# MotorController_ToniDove_Full06.net
KiCad netlist of a schematic drawn in EAGLE
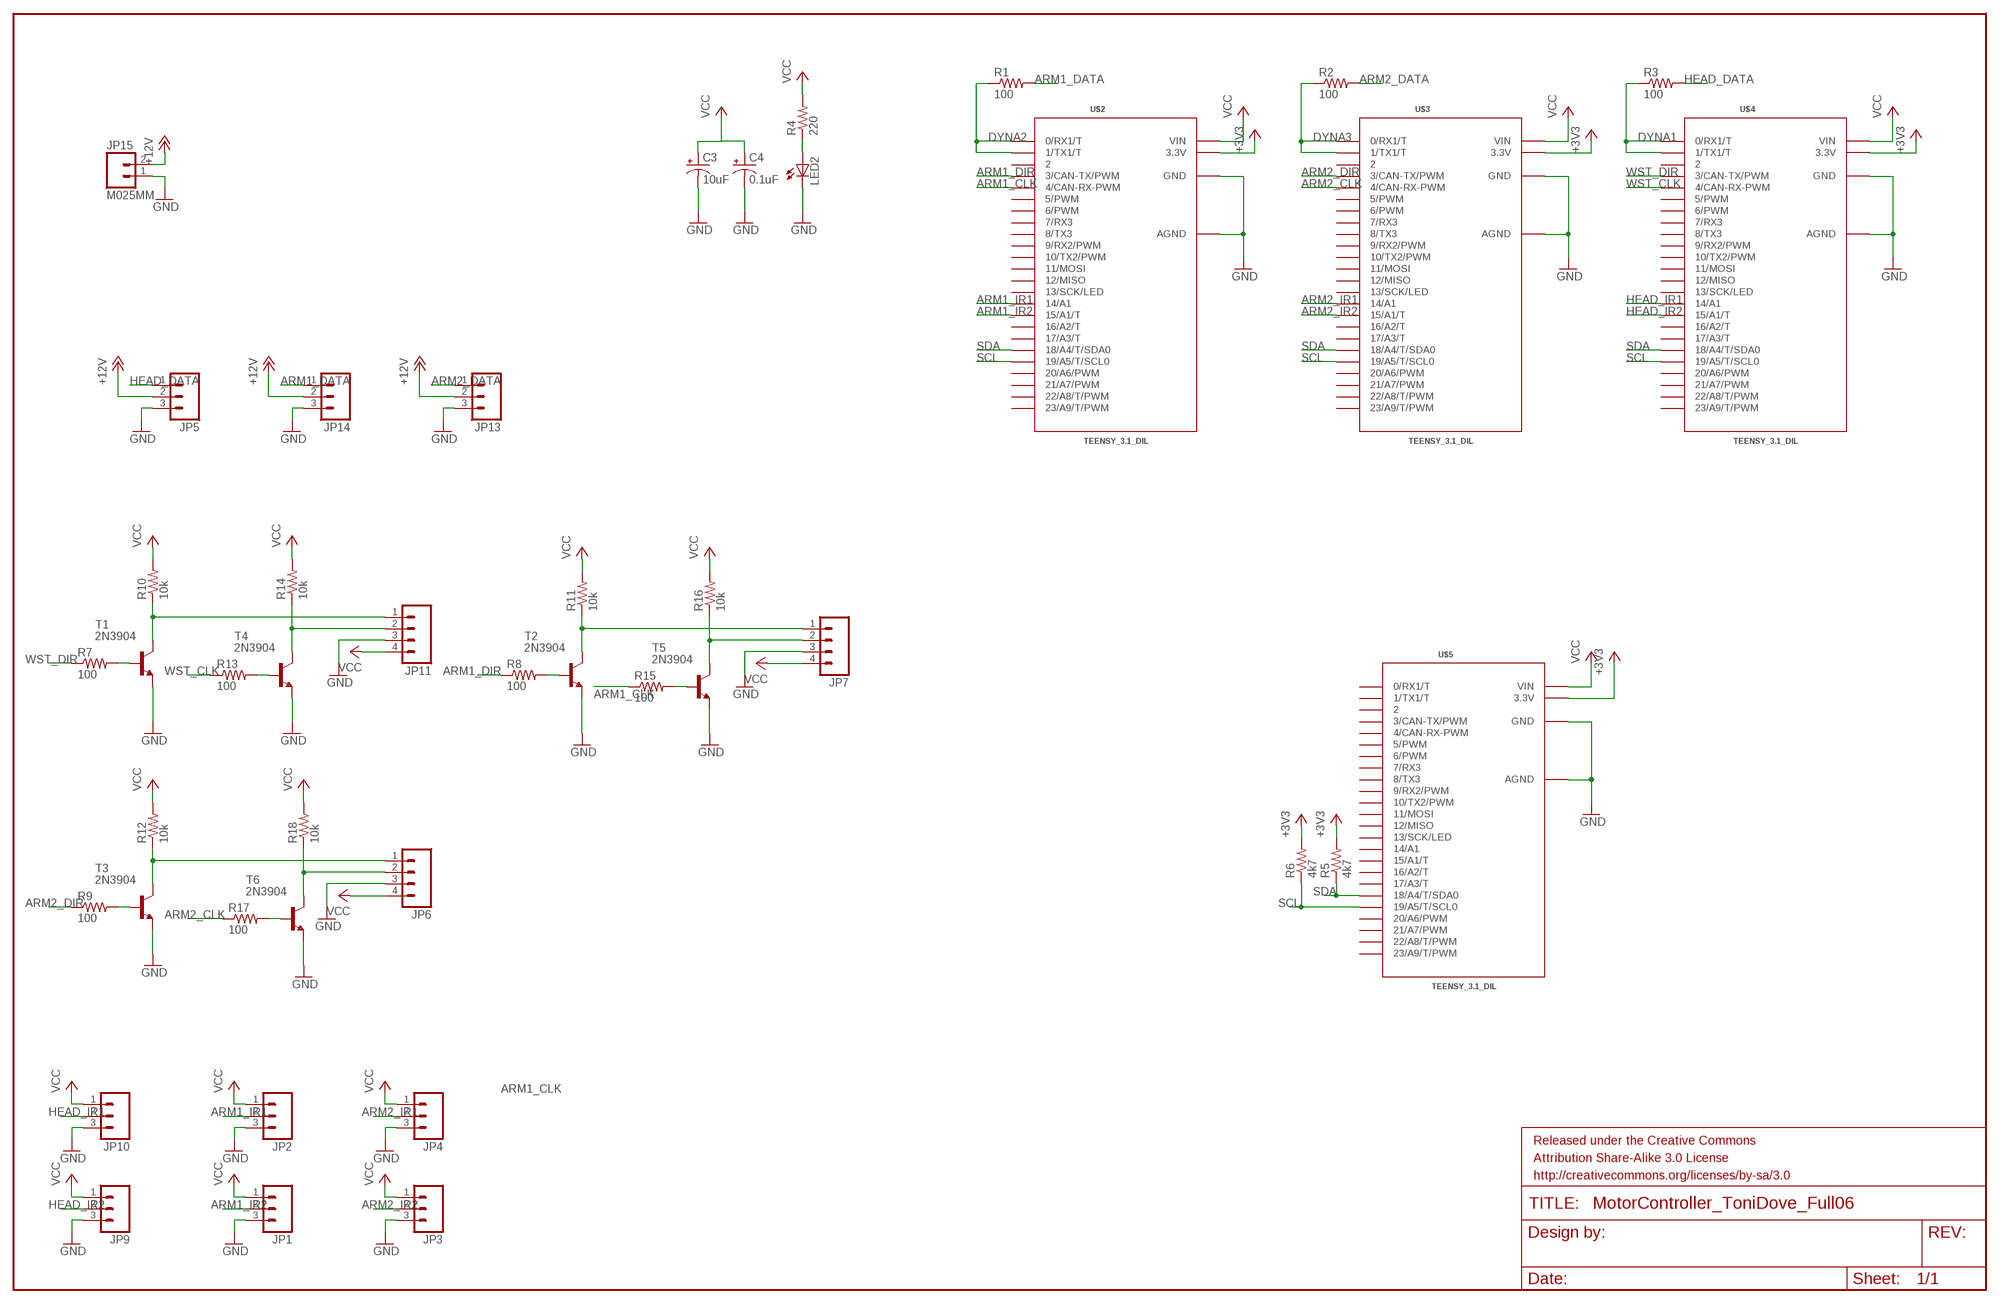
[diagram p0: schematic, sheet 1]

(export (version "E")
  (design (tool "Eeschema 10.0.6"))
  (components
    (comp (ref "C3")
      (value "10uF")
      (footprint "eagle-import:E2,5-6E")
      (libsource (lib "eagle-import") (part "CPOL-USE2,5-6E"))
    )
    (comp (ref "C4")
      (value "0.1uF")
      (footprint "eagle-import:E2,5-6E")
      (libsource (lib "eagle-import") (part "CPOL-USE2,5-6E"))
    )
    (comp (ref "FRAME1")
      (value "FRAME-LEDGER")
      (footprint "eagle-import:CREATIVE_COMMONS")
      (libsource (lib "eagle-import") (part "FRAME-LEDGER"))
    )
    (comp (ref "JP1")
      (value "M03PTH")
      (footprint "eagle-import:1X03")
      (libsource (lib "eagle-import") (part "M03PTH"))
    )
    (comp (ref "JP2")
      (value "M03PTH")
      (footprint "eagle-import:1X03")
      (libsource (lib "eagle-import") (part "M03PTH"))
    )
    (comp (ref "JP3")
      (value "M03PTH")
      (footprint "eagle-import:1X03")
      (libsource (lib "eagle-import") (part "M03PTH"))
    )
    (comp (ref "JP4")
      (value "M03PTH")
      (footprint "eagle-import:1X03")
      (libsource (lib "eagle-import") (part "M03PTH"))
    )
    (comp (ref "JP5")
      (value "M03PTH")
      (footprint "eagle-import:1X03")
      (libsource (lib "eagle-import") (part "M03PTH"))
    )
    (comp (ref "JP6")
      (value "M04SCREW")
      (footprint "eagle-import:SCREWTERMINAL-3.5MM-4")
      (libsource (lib "eagle-import") (part "M04SCREW"))
    )
    (comp (ref "JP7")
      (value "M04SCREW")
      (footprint "eagle-import:SCREWTERMINAL-3.5MM-4")
      (libsource (lib "eagle-import") (part "M04SCREW"))
    )
    (comp (ref "JP9")
      (value "M03PTH")
      (footprint "eagle-import:1X03")
      (libsource (lib "eagle-import") (part "M03PTH"))
    )
    (comp (ref "JP10")
      (value "M03PTH")
      (footprint "eagle-import:1X03")
      (libsource (lib "eagle-import") (part "M03PTH"))
    )
    (comp (ref "JP11")
      (value "M04SCREW")
      (footprint "eagle-import:SCREWTERMINAL-3.5MM-4")
      (libsource (lib "eagle-import") (part "M04SCREW"))
    )
    (comp (ref "JP13")
      (value "M03PTH")
      (footprint "eagle-import:1X03")
      (libsource (lib "eagle-import") (part "M03PTH"))
    )
    (comp (ref "JP14")
      (value "M03PTH")
      (footprint "eagle-import:1X03")
      (libsource (lib "eagle-import") (part "M03PTH"))
    )
    (comp (ref "JP15")
      (value "M025MM")
      (footprint "eagle-import:SCREWTERMINAL-5MM-2")
      (libsource (lib "eagle-import") (part "M025MM"))
    )
    (comp (ref "LED2")
      (value "LED5MM")
      (footprint "eagle-import:LED5MM")
      (libsource (lib "eagle-import") (part "LED5MM"))
    )
    (comp (ref "R1")
      (value "100")
      (footprint "eagle-import:0204_7")
      (libsource (lib "eagle-import") (part "R-US_0204/7"))
    )
    (comp (ref "R2")
      (value "100")
      (footprint "eagle-import:0204_7")
      (libsource (lib "eagle-import") (part "R-US_0204/7"))
    )
    (comp (ref "R3")
      (value "100")
      (footprint "eagle-import:0204_7")
      (libsource (lib "eagle-import") (part "R-US_0204/7"))
    )
    (comp (ref "R4")
      (value "220")
      (footprint "eagle-import:0204_7")
      (libsource (lib "eagle-import") (part "R-US_0204/7"))
    )
    (comp (ref "R5")
      (value "4k7")
      (footprint "eagle-import:0204_7")
      (libsource (lib "eagle-import") (part "R-US_0204/7"))
    )
    (comp (ref "R6")
      (value "4k7")
      (footprint "eagle-import:0204_7")
      (libsource (lib "eagle-import") (part "R-US_0204/7"))
    )
    (comp (ref "R7")
      (value "100")
      (footprint "eagle-import:0204_7")
      (libsource (lib "eagle-import") (part "R-US_0204/7"))
    )
    (comp (ref "R8")
      (value "100")
      (footprint "eagle-import:0204_7")
      (libsource (lib "eagle-import") (part "R-US_0204/7"))
    )
    (comp (ref "R9")
      (value "100")
      (footprint "eagle-import:0204_7")
      (libsource (lib "eagle-import") (part "R-US_0204/7"))
    )
    (comp (ref "R10")
      (value "10k")
      (footprint "eagle-import:0204_7")
      (libsource (lib "eagle-import") (part "R-US_0204/7"))
    )
    (comp (ref "R11")
      (value "10k")
      (footprint "eagle-import:0204_7")
      (libsource (lib "eagle-import") (part "R-US_0204/7"))
    )
    (comp (ref "R12")
      (value "10k")
      (footprint "eagle-import:0204_7")
      (libsource (lib "eagle-import") (part "R-US_0204/7"))
    )
    (comp (ref "R13")
      (value "100")
      (footprint "eagle-import:0204_7")
      (libsource (lib "eagle-import") (part "R-US_0204/7"))
    )
    (comp (ref "R14")
      (value "10k")
      (footprint "eagle-import:0204_7")
      (libsource (lib "eagle-import") (part "R-US_0204/7"))
    )
    (comp (ref "R15")
      (value "100")
      (footprint "eagle-import:0204_7")
      (libsource (lib "eagle-import") (part "R-US_0204/7"))
    )
    (comp (ref "R16")
      (value "10k")
      (footprint "eagle-import:0204_7")
      (libsource (lib "eagle-import") (part "R-US_0204/7"))
    )
    (comp (ref "R17")
      (value "100")
      (footprint "eagle-import:0204_7")
      (libsource (lib "eagle-import") (part "R-US_0204/7"))
    )
    (comp (ref "R18")
      (value "10k")
      (footprint "eagle-import:0204_7")
      (libsource (lib "eagle-import") (part "R-US_0204/7"))
    )
    (comp (ref "T1")
      (value "2N3904")
      (footprint "eagle-import:TO92")
      (libsource (lib "eagle-import") (part "2N3904"))
    )
    (comp (ref "T2")
      (value "2N3904")
      (footprint "eagle-import:TO92")
      (libsource (lib "eagle-import") (part "2N3904"))
    )
    (comp (ref "T3")
      (value "2N3904")
      (footprint "eagle-import:TO92")
      (libsource (lib "eagle-import") (part "2N3904"))
    )
    (comp (ref "T4")
      (value "2N3904")
      (footprint "eagle-import:TO92")
      (libsource (lib "eagle-import") (part "2N3904"))
    )
    (comp (ref "T5")
      (value "2N3904")
      (footprint "eagle-import:TO92")
      (libsource (lib "eagle-import") (part "2N3904"))
    )
    (comp (ref "T6")
      (value "2N3904")
      (footprint "eagle-import:TO92")
      (libsource (lib "eagle-import") (part "2N3904"))
    )
    (comp (ref "U$2")
      (value "TEENSY_3.1_DIL")
      (footprint "eagle-import:TEENSY3-DIL")
      (libsource (lib "eagle-import") (part "TEENSY_3.1_DIL"))
    )
    (comp (ref "U$3")
      (value "TEENSY_3.1_DIL")
      (footprint "eagle-import:TEENSY3-DIL")
      (libsource (lib "eagle-import") (part "TEENSY_3.1_DIL"))
    )
    (comp (ref "U$4")
      (value "TEENSY_3.1_DIL")
      (footprint "eagle-import:TEENSY3-DIL")
      (libsource (lib "eagle-import") (part "TEENSY_3.1_DIL"))
    )
    (comp (ref "U$5")
      (value "TEENSY_3.1_DIL")
      (footprint "eagle-import:TEENSY3-DIL")
      (libsource (lib "eagle-import") (part "TEENSY_3.1_DIL"))
    )
  )
  (nets
    (net (code "1") (name "+3V3") (class "Default")
      (node (ref "R5") (pin "2") (pinfunction "2_2") (pintype "passive"))
      (node (ref "R6") (pin "2") (pinfunction "2_2") (pintype "passive"))
      (node (ref "U$2") (pin "3.3V") (pinfunction "3.3V_3.3V") (pintype "power_in"))
      (node (ref "U$3") (pin "3.3V") (pinfunction "3.3V_3.3V") (pintype "power_in"))
      (node (ref "U$4") (pin "3.3V") (pinfunction "3.3V_3.3V") (pintype "power_in"))
      (node (ref "U$5") (pin "3.3V") (pinfunction "3.3V_3.3V") (pintype "power_in"))
    )
    (net (code "2") (name "+12V") (class "Default")
      (node (ref "JP13") (pin "2") (pinfunction "2_2") (pintype "passive"))
      (node (ref "JP14") (pin "2") (pinfunction "2_2") (pintype "passive"))
      (node (ref "JP15") (pin "2") (pinfunction "2_2") (pintype "passive"))
      (node (ref "JP5") (pin "2") (pinfunction "2_2") (pintype "passive"))
    )
    (net (code "3") (name "/ARM1_CLK") (class "Default")
      (node (ref "R15") (pin "1") (pinfunction "1_1") (pintype "passive"))
      (node (ref "U$2") (pin "4") (pinfunction "4/CAN-RX-PWM_4") (pintype "bidirectional"))
    )
    (net (code "4") (name "/ARM1_DATA") (class "Default")
      (node (ref "JP14") (pin "1") (pinfunction "1_1") (pintype "passive"))
      (node (ref "R1") (pin "2") (pinfunction "2_2") (pintype "passive"))
    )
    (net (code "5") (name "/ARM1_DIR") (class "Default")
      (node (ref "R8") (pin "1") (pinfunction "1_1") (pintype "passive"))
      (node (ref "U$2") (pin "3") (pinfunction "3/CAN-TX/PWM_3") (pintype "bidirectional"))
    )
    (net (code "6") (name "/ARM1_IR1") (class "Default")
      (node (ref "JP2") (pin "2") (pinfunction "2_2") (pintype "passive"))
      (node (ref "U$2") (pin "14/A0") (pinfunction "14/A1_14/A0") (pintype "bidirectional"))
    )
    (net (code "7") (name "/ARM1_IR2") (class "Default")
      (node (ref "JP1") (pin "2") (pinfunction "2_2") (pintype "passive"))
      (node (ref "U$2") (pin "15/A1") (pinfunction "15/A1/T_15/A1") (pintype "bidirectional"))
    )
    (net (code "8") (name "/ARM2_CLK") (class "Default")
      (node (ref "R17") (pin "1") (pinfunction "1_1") (pintype "passive"))
      (node (ref "U$3") (pin "4") (pinfunction "4/CAN-RX-PWM_4") (pintype "bidirectional"))
    )
    (net (code "9") (name "/ARM2_DATA") (class "Default")
      (node (ref "JP13") (pin "1") (pinfunction "1_1") (pintype "passive"))
      (node (ref "R2") (pin "2") (pinfunction "2_2") (pintype "passive"))
    )
    (net (code "10") (name "/ARM2_DIR") (class "Default")
      (node (ref "R9") (pin "1") (pinfunction "1_1") (pintype "passive"))
      (node (ref "U$3") (pin "3") (pinfunction "3/CAN-TX/PWM_3") (pintype "bidirectional"))
    )
    (net (code "11") (name "/ARM2_IR1") (class "Default")
      (node (ref "JP4") (pin "2") (pinfunction "2_2") (pintype "passive"))
      (node (ref "U$3") (pin "14/A0") (pinfunction "14/A1_14/A0") (pintype "bidirectional"))
    )
    (net (code "12") (name "/ARM2_IR2") (class "Default")
      (node (ref "JP3") (pin "2") (pinfunction "2_2") (pintype "passive"))
      (node (ref "U$3") (pin "15/A1") (pinfunction "15/A1/T_15/A1") (pintype "bidirectional"))
    )
    (net (code "13") (name "/DYNA1") (class "Default")
      (node (ref "R3") (pin "1") (pinfunction "1_1") (pintype "passive"))
      (node (ref "U$4") (pin "0") (pinfunction "0/RX1/T_0") (pintype "bidirectional"))
      (node (ref "U$4") (pin "1") (pinfunction "1/TX1/T_1") (pintype "bidirectional"))
    )
    (net (code "14") (name "/DYNA2") (class "Default")
      (node (ref "R1") (pin "1") (pinfunction "1_1") (pintype "passive"))
      (node (ref "U$2") (pin "0") (pinfunction "0/RX1/T_0") (pintype "bidirectional"))
      (node (ref "U$2") (pin "1") (pinfunction "1/TX1/T_1") (pintype "bidirectional"))
    )
    (net (code "15") (name "/DYNA3") (class "Default")
      (node (ref "R2") (pin "1") (pinfunction "1_1") (pintype "passive"))
      (node (ref "U$3") (pin "0") (pinfunction "0/RX1/T_0") (pintype "bidirectional"))
      (node (ref "U$3") (pin "1") (pinfunction "1/TX1/T_1") (pintype "bidirectional"))
    )
    (net (code "16") (name "/HEAD_DATA") (class "Default")
      (node (ref "JP5") (pin "1") (pinfunction "1_1") (pintype "passive"))
      (node (ref "R3") (pin "2") (pinfunction "2_2") (pintype "passive"))
    )
    (net (code "17") (name "/HEAD_IR1") (class "Default")
      (node (ref "JP10") (pin "2") (pinfunction "2_2") (pintype "passive"))
      (node (ref "U$4") (pin "14/A0") (pinfunction "14/A1_14/A0") (pintype "bidirectional"))
    )
    (net (code "18") (name "/HEAD_IR2") (class "Default")
      (node (ref "JP9") (pin "2") (pinfunction "2_2") (pintype "passive"))
      (node (ref "U$4") (pin "15/A1") (pinfunction "15/A1/T_15/A1") (pintype "bidirectional"))
    )
    (net (code "19") (name "/SCL") (class "Default")
      (node (ref "R6") (pin "1") (pinfunction "1_1") (pintype "passive"))
      (node (ref "U$2") (pin "19/A5") (pinfunction "19/A5/T/SCL0_19/A5") (pintype "bidirectional"))
      (node (ref "U$3") (pin "19/A5") (pinfunction "19/A5/T/SCL0_19/A5") (pintype "bidirectional"))
      (node (ref "U$4") (pin "19/A5") (pinfunction "19/A5/T/SCL0_19/A5") (pintype "bidirectional"))
      (node (ref "U$5") (pin "19/A5") (pinfunction "19/A5/T/SCL0_19/A5") (pintype "bidirectional"))
    )
    (net (code "20") (name "/SDA") (class "Default")
      (node (ref "R5") (pin "1") (pinfunction "1_1") (pintype "passive"))
      (node (ref "U$2") (pin "18/A4") (pinfunction "18/A4/T/SDA0_18/A4") (pintype "bidirectional"))
      (node (ref "U$3") (pin "18/A4") (pinfunction "18/A4/T/SDA0_18/A4") (pintype "bidirectional"))
      (node (ref "U$4") (pin "18/A4") (pinfunction "18/A4/T/SDA0_18/A4") (pintype "bidirectional"))
      (node (ref "U$5") (pin "18/A4") (pinfunction "18/A4/T/SDA0_18/A4") (pintype "bidirectional"))
    )
    (net (code "21") (name "/WST_CLK") (class "Default")
      (node (ref "R13") (pin "1") (pinfunction "1_1") (pintype "passive"))
      (node (ref "U$4") (pin "4") (pinfunction "4/CAN-RX-PWM_4") (pintype "bidirectional"))
    )
    (net (code "22") (name "/WST_DIR") (class "Default")
      (node (ref "R7") (pin "1") (pinfunction "1_1") (pintype "passive"))
      (node (ref "U$4") (pin "3") (pinfunction "3/CAN-TX/PWM_3") (pintype "bidirectional"))
    )
    (net (code "23") (name "GND") (class "Default")
      (node (ref "C3") (pin "-") (pinfunction "-_-") (pintype "passive"))
      (node (ref "C4") (pin "-") (pinfunction "-_-") (pintype "passive"))
      (node (ref "JP1") (pin "3") (pinfunction "3_3") (pintype "passive"))
      (node (ref "JP10") (pin "3") (pinfunction "3_3") (pintype "passive"))
      (node (ref "JP11") (pin "3") (pinfunction "3_3") (pintype "passive"))
      (node (ref "JP13") (pin "3") (pinfunction "3_3") (pintype "passive"))
      (node (ref "JP14") (pin "3") (pinfunction "3_3") (pintype "passive"))
      (node (ref "JP15") (pin "1") (pinfunction "1_1") (pintype "passive"))
      (node (ref "JP2") (pin "3") (pinfunction "3_3") (pintype "passive"))
      (node (ref "JP3") (pin "3") (pinfunction "3_3") (pintype "passive"))
      (node (ref "JP4") (pin "3") (pinfunction "3_3") (pintype "passive"))
      (node (ref "JP5") (pin "3") (pinfunction "3_3") (pintype "passive"))
      (node (ref "JP6") (pin "3") (pinfunction "3_3") (pintype "passive"))
      (node (ref "JP7") (pin "3") (pinfunction "3_3") (pintype "passive"))
      (node (ref "JP9") (pin "3") (pinfunction "3_3") (pintype "passive"))
      (node (ref "LED2") (pin "K") (pinfunction "C_K") (pintype "passive"))
      (node (ref "T1") (pin "3") (pinfunction "E_3") (pintype "passive"))
      (node (ref "T2") (pin "3") (pinfunction "E_3") (pintype "passive"))
      (node (ref "T3") (pin "3") (pinfunction "E_3") (pintype "passive"))
      (node (ref "T4") (pin "3") (pinfunction "E_3") (pintype "passive"))
      (node (ref "T5") (pin "3") (pinfunction "E_3") (pintype "passive"))
      (node (ref "T6") (pin "3") (pinfunction "E_3") (pintype "passive"))
      (node (ref "U$2") (pin "AGND") (pinfunction "AGND_AGND") (pintype "power_in"))
      (node (ref "U$2") (pin "GND") (pinfunction "GND_GND") (pintype "power_in"))
      (node (ref "U$3") (pin "AGND") (pinfunction "AGND_AGND") (pintype "power_in"))
      (node (ref "U$3") (pin "GND") (pinfunction "GND_GND") (pintype "power_in"))
      (node (ref "U$4") (pin "AGND") (pinfunction "AGND_AGND") (pintype "power_in"))
      (node (ref "U$4") (pin "GND") (pinfunction "GND_GND") (pintype "power_in"))
      (node (ref "U$5") (pin "AGND") (pinfunction "AGND_AGND") (pintype "power_in"))
      (node (ref "U$5") (pin "GND") (pinfunction "GND_GND") (pintype "power_in"))
    )
    (net (code "24") (name "Net-(LED2-PadA)") (class "Default")
      (node (ref "LED2") (pin "A") (pinfunction "A_A") (pintype "passive"))
      (node (ref "R4") (pin "1") (pinfunction "1_1") (pintype "passive"))
    )
    (net (code "25") (name "Net-(T1-B)") (class "Default")
      (node (ref "R7") (pin "2") (pinfunction "2_2") (pintype "passive"))
      (node (ref "T1") (pin "2") (pinfunction "B_2") (pintype "passive"))
    )
    (net (code "26") (name "Net-(T1-C)") (class "Default")
      (node (ref "JP11") (pin "1") (pinfunction "1_1") (pintype "passive"))
      (node (ref "R10") (pin "1") (pinfunction "1_1") (pintype "passive"))
      (node (ref "T1") (pin "1") (pinfunction "C_1") (pintype "passive"))
    )
    (net (code "27") (name "Net-(T2-B)") (class "Default")
      (node (ref "R8") (pin "2") (pinfunction "2_2") (pintype "passive"))
      (node (ref "T2") (pin "2") (pinfunction "B_2") (pintype "passive"))
    )
    (net (code "28") (name "Net-(T2-C)") (class "Default")
      (node (ref "JP7") (pin "1") (pinfunction "1_1") (pintype "passive"))
      (node (ref "R11") (pin "1") (pinfunction "1_1") (pintype "passive"))
      (node (ref "T2") (pin "1") (pinfunction "C_1") (pintype "passive"))
    )
    (net (code "29") (name "Net-(T3-B)") (class "Default")
      (node (ref "R9") (pin "2") (pinfunction "2_2") (pintype "passive"))
      (node (ref "T3") (pin "2") (pinfunction "B_2") (pintype "passive"))
    )
    (net (code "30") (name "Net-(T3-C)") (class "Default")
      (node (ref "JP6") (pin "1") (pinfunction "1_1") (pintype "passive"))
      (node (ref "R12") (pin "1") (pinfunction "1_1") (pintype "passive"))
      (node (ref "T3") (pin "1") (pinfunction "C_1") (pintype "passive"))
    )
    (net (code "31") (name "Net-(T4-B)") (class "Default")
      (node (ref "R13") (pin "2") (pinfunction "2_2") (pintype "passive"))
      (node (ref "T4") (pin "2") (pinfunction "B_2") (pintype "passive"))
    )
    (net (code "32") (name "Net-(T4-C)") (class "Default")
      (node (ref "JP11") (pin "2") (pinfunction "2_2") (pintype "passive"))
      (node (ref "R14") (pin "1") (pinfunction "1_1") (pintype "passive"))
      (node (ref "T4") (pin "1") (pinfunction "C_1") (pintype "passive"))
    )
    (net (code "33") (name "Net-(T5-B)") (class "Default")
      (node (ref "R15") (pin "2") (pinfunction "2_2") (pintype "passive"))
      (node (ref "T5") (pin "2") (pinfunction "B_2") (pintype "passive"))
    )
    (net (code "34") (name "Net-(T5-C)") (class "Default")
      (node (ref "JP7") (pin "2") (pinfunction "2_2") (pintype "passive"))
      (node (ref "R16") (pin "1") (pinfunction "1_1") (pintype "passive"))
      (node (ref "T5") (pin "1") (pinfunction "C_1") (pintype "passive"))
    )
    (net (code "35") (name "Net-(T6-B)") (class "Default")
      (node (ref "R17") (pin "2") (pinfunction "2_2") (pintype "passive"))
      (node (ref "T6") (pin "2") (pinfunction "B_2") (pintype "passive"))
    )
    (net (code "36") (name "Net-(T6-C)") (class "Default")
      (node (ref "JP6") (pin "2") (pinfunction "2_2") (pintype "passive"))
      (node (ref "R18") (pin "1") (pinfunction "1_1") (pintype "passive"))
      (node (ref "T6") (pin "1") (pinfunction "C_1") (pintype "passive"))
    )
    (net (code "37") (name "VCC") (class "Default")
      (node (ref "C3") (pin "+") (pinfunction "+_+") (pintype "passive"))
      (node (ref "C4") (pin "+") (pinfunction "+_+") (pintype "passive"))
      (node (ref "JP1") (pin "1") (pinfunction "1_1") (pintype "passive"))
      (node (ref "JP10") (pin "1") (pinfunction "1_1") (pintype "passive"))
      (node (ref "JP11") (pin "4") (pinfunction "4_4") (pintype "passive"))
      (node (ref "JP2") (pin "1") (pinfunction "1_1") (pintype "passive"))
      (node (ref "JP3") (pin "1") (pinfunction "1_1") (pintype "passive"))
      (node (ref "JP4") (pin "1") (pinfunction "1_1") (pintype "passive"))
      (node (ref "JP6") (pin "4") (pinfunction "4_4") (pintype "passive"))
      (node (ref "JP7") (pin "4") (pinfunction "4_4") (pintype "passive"))
      (node (ref "JP9") (pin "1") (pinfunction "1_1") (pintype "passive"))
      (node (ref "R10") (pin "2") (pinfunction "2_2") (pintype "passive"))
      (node (ref "R11") (pin "2") (pinfunction "2_2") (pintype "passive"))
      (node (ref "R12") (pin "2") (pinfunction "2_2") (pintype "passive"))
      (node (ref "R14") (pin "2") (pinfunction "2_2") (pintype "passive"))
      (node (ref "R16") (pin "2") (pinfunction "2_2") (pintype "passive"))
      (node (ref "R18") (pin "2") (pinfunction "2_2") (pintype "passive"))
      (node (ref "R4") (pin "2") (pinfunction "2_2") (pintype "passive"))
      (node (ref "U$2") (pin "VIN") (pinfunction "VIN_VIN") (pintype "power_in"))
      (node (ref "U$3") (pin "VIN") (pinfunction "VIN_VIN") (pintype "power_in"))
      (node (ref "U$4") (pin "VIN") (pinfunction "VIN_VIN") (pintype "power_in"))
      (node (ref "U$5") (pin "VIN") (pinfunction "VIN_VIN") (pintype "power_in"))
    )
    (net (code "38") (name "unconnected-(U$2-5{slash}PWM-Pad5)") (class "Default")
      (node (ref "U$2") (pin "5") (pinfunction "5/PWM_5") (pintype "bidirectional"))
    )
    (net (code "39") (name "unconnected-(U$2-6{slash}PWM-Pad6)") (class "Default")
      (node (ref "U$2") (pin "6") (pinfunction "6/PWM_6") (pintype "bidirectional"))
    )
    (net (code "40") (name "unconnected-(U$2-7{slash}RX3-Pad7)") (class "Default")
      (node (ref "U$2") (pin "7") (pinfunction "7/RX3_7") (pintype "bidirectional"))
    )
    (net (code "41") (name "unconnected-(U$2-8{slash}TX3-Pad8)") (class "Default")
      (node (ref "U$2") (pin "8") (pinfunction "8/TX3_8") (pintype "bidirectional"))
    )
    (net (code "42") (name "unconnected-(U$2-9{slash}RX2{slash}PWM-Pad9)") (class "Default")
      (node (ref "U$2") (pin "9") (pinfunction "9/RX2/PWM_9") (pintype "bidirectional"))
    )
    (net (code "43") (name "unconnected-(U$2-10{slash}TX2{slash}PWM-Pad10)") (class "Default")
      (node (ref "U$2") (pin "10") (pinfunction "10/TX2/PWM_10") (pintype "bidirectional"))
    )
    (net (code "44") (name "unconnected-(U$2-11{slash}MOSI-Pad11)") (class "Default")
      (node (ref "U$2") (pin "11") (pinfunction "11/MOSI_11") (pintype "bidirectional"))
    )
    (net (code "45") (name "unconnected-(U$2-12{slash}MISO-Pad12)") (class "Default")
      (node (ref "U$2") (pin "12") (pinfunction "12/MISO_12") (pintype "bidirectional"))
    )
    (net (code "46") (name "unconnected-(U$2-13{slash}SCK{slash}LED-Pad13)") (class "Default")
      (node (ref "U$2") (pin "13") (pinfunction "13/SCK/LED_13") (pintype "bidirectional"))
    )
    (net (code "47") (name "unconnected-(U$2-16{slash}A2{slash}T-Pad16{slash}A2)") (class "Default")
      (node (ref "U$2") (pin "16/A2") (pinfunction "16/A2/T_16/A2") (pintype "bidirectional"))
    )
    (net (code "48") (name "unconnected-(U$2-17{slash}A3{slash}T-Pad17{slash}A3)") (class "Default")
      (node (ref "U$2") (pin "17/A3") (pinfunction "17/A3/T_17/A3") (pintype "bidirectional"))
    )
    (net (code "49") (name "unconnected-(U$2-20{slash}A6{slash}PWM-Pad20{slash}A6)") (class "Default")
      (node (ref "U$2") (pin "20/A6") (pinfunction "20/A6/PWM_20/A6") (pintype "bidirectional"))
    )
    (net (code "50") (name "unconnected-(U$2-21{slash}A7{slash}PWM-Pad21{slash}A7)") (class "Default")
      (node (ref "U$2") (pin "21/A7") (pinfunction "21/A7/PWM_21/A7") (pintype "bidirectional"))
    )
    (net (code "51") (name "unconnected-(U$2-22{slash}A8{slash}T{slash}PWM-Pad22{slash}A8)") (class "Default")
      (node (ref "U$2") (pin "22/A8") (pinfunction "22/A8/T/PWM_22/A8") (pintype "bidirectional"))
    )
    (net (code "52") (name "unconnected-(U$2-23{slash}A9{slash}T{slash}PWM-Pad23{slash}A9)") (class "Default")
      (node (ref "U$2") (pin "23/A9") (pinfunction "23/A9/T/PWM_23/A9") (pintype "bidirectional"))
    )
    (net (code "53") (name "unconnected-(U$2-Pad2)") (class "Default")
      (node (ref "U$2") (pin "2") (pinfunction "2_2") (pintype "bidirectional"))
    )
    (net (code "54") (name "unconnected-(U$3-5{slash}PWM-Pad5)") (class "Default")
      (node (ref "U$3") (pin "5") (pinfunction "5/PWM_5") (pintype "bidirectional"))
    )
    (net (code "55") (name "unconnected-(U$3-6{slash}PWM-Pad6)") (class "Default")
      (node (ref "U$3") (pin "6") (pinfunction "6/PWM_6") (pintype "bidirectional"))
    )
    (net (code "56") (name "unconnected-(U$3-7{slash}RX3-Pad7)") (class "Default")
      (node (ref "U$3") (pin "7") (pinfunction "7/RX3_7") (pintype "bidirectional"))
    )
    (net (code "57") (name "unconnected-(U$3-8{slash}TX3-Pad8)") (class "Default")
      (node (ref "U$3") (pin "8") (pinfunction "8/TX3_8") (pintype "bidirectional"))
    )
    (net (code "58") (name "unconnected-(U$3-9{slash}RX2{slash}PWM-Pad9)") (class "Default")
      (node (ref "U$3") (pin "9") (pinfunction "9/RX2/PWM_9") (pintype "bidirectional"))
    )
    (net (code "59") (name "unconnected-(U$3-10{slash}TX2{slash}PWM-Pad10)") (class "Default")
      (node (ref "U$3") (pin "10") (pinfunction "10/TX2/PWM_10") (pintype "bidirectional"))
    )
    (net (code "60") (name "unconnected-(U$3-11{slash}MOSI-Pad11)") (class "Default")
      (node (ref "U$3") (pin "11") (pinfunction "11/MOSI_11") (pintype "bidirectional"))
    )
    (net (code "61") (name "unconnected-(U$3-12{slash}MISO-Pad12)") (class "Default")
      (node (ref "U$3") (pin "12") (pinfunction "12/MISO_12") (pintype "bidirectional"))
    )
    (net (code "62") (name "unconnected-(U$3-13{slash}SCK{slash}LED-Pad13)") (class "Default")
      (node (ref "U$3") (pin "13") (pinfunction "13/SCK/LED_13") (pintype "bidirectional"))
    )
    (net (code "63") (name "unconnected-(U$3-16{slash}A2{slash}T-Pad16{slash}A2)") (class "Default")
      (node (ref "U$3") (pin "16/A2") (pinfunction "16/A2/T_16/A2") (pintype "bidirectional"))
    )
    (net (code "64") (name "unconnected-(U$3-17{slash}A3{slash}T-Pad17{slash}A3)") (class "Default")
      (node (ref "U$3") (pin "17/A3") (pinfunction "17/A3/T_17/A3") (pintype "bidirectional"))
    )
    (net (code "65") (name "unconnected-(U$3-20{slash}A6{slash}PWM-Pad20{slash}A6)") (class "Default")
      (node (ref "U$3") (pin "20/A6") (pinfunction "20/A6/PWM_20/A6") (pintype "bidirectional"))
    )
    (net (code "66") (name "unconnected-(U$3-21{slash}A7{slash}PWM-Pad21{slash}A7)") (class "Default")
      (node (ref "U$3") (pin "21/A7") (pinfunction "21/A7/PWM_21/A7") (pintype "bidirectional"))
    )
    (net (code "67") (name "unconnected-(U$3-22{slash}A8{slash}T{slash}PWM-Pad22{slash}A8)") (class "Default")
      (node (ref "U$3") (pin "22/A8") (pinfunction "22/A8/T/PWM_22/A8") (pintype "bidirectional"))
    )
    (net (code "68") (name "unconnected-(U$3-23{slash}A9{slash}T{slash}PWM-Pad23{slash}A9)") (class "Default")
      (node (ref "U$3") (pin "23/A9") (pinfunction "23/A9/T/PWM_23/A9") (pintype "bidirectional"))
    )
    (net (code "69") (name "unconnected-(U$3-Pad2)") (class "Default")
      (node (ref "U$3") (pin "2") (pinfunction "2_2") (pintype "bidirectional"))
    )
    (net (code "70") (name "unconnected-(U$4-5{slash}PWM-Pad5)") (class "Default")
      (node (ref "U$4") (pin "5") (pinfunction "5/PWM_5") (pintype "bidirectional"))
    )
    (net (code "71") (name "unconnected-(U$4-6{slash}PWM-Pad6)") (class "Default")
      (node (ref "U$4") (pin "6") (pinfunction "6/PWM_6") (pintype "bidirectional"))
    )
    (net (code "72") (name "unconnected-(U$4-7{slash}RX3-Pad7)") (class "Default")
      (node (ref "U$4") (pin "7") (pinfunction "7/RX3_7") (pintype "bidirectional"))
    )
    (net (code "73") (name "unconnected-(U$4-8{slash}TX3-Pad8)") (class "Default")
      (node (ref "U$4") (pin "8") (pinfunction "8/TX3_8") (pintype "bidirectional"))
    )
    (net (code "74") (name "unconnected-(U$4-9{slash}RX2{slash}PWM-Pad9)") (class "Default")
      (node (ref "U$4") (pin "9") (pinfunction "9/RX2/PWM_9") (pintype "bidirectional"))
    )
    (net (code "75") (name "unconnected-(U$4-10{slash}TX2{slash}PWM-Pad10)") (class "Default")
      (node (ref "U$4") (pin "10") (pinfunction "10/TX2/PWM_10") (pintype "bidirectional"))
    )
    (net (code "76") (name "unconnected-(U$4-11{slash}MOSI-Pad11)") (class "Default")
      (node (ref "U$4") (pin "11") (pinfunction "11/MOSI_11") (pintype "bidirectional"))
    )
    (net (code "77") (name "unconnected-(U$4-12{slash}MISO-Pad12)") (class "Default")
      (node (ref "U$4") (pin "12") (pinfunction "12/MISO_12") (pintype "bidirectional"))
    )
    (net (code "78") (name "unconnected-(U$4-13{slash}SCK{slash}LED-Pad13)") (class "Default")
      (node (ref "U$4") (pin "13") (pinfunction "13/SCK/LED_13") (pintype "bidirectional"))
    )
    (net (code "79") (name "unconnected-(U$4-16{slash}A2{slash}T-Pad16{slash}A2)") (class "Default")
      (node (ref "U$4") (pin "16/A2") (pinfunction "16/A2/T_16/A2") (pintype "bidirectional"))
    )
    (net (code "80") (name "unconnected-(U$4-17{slash}A3{slash}T-Pad17{slash}A3)") (class "Default")
      (node (ref "U$4") (pin "17/A3") (pinfunction "17/A3/T_17/A3") (pintype "bidirectional"))
    )
    (net (code "81") (name "unconnected-(U$4-20{slash}A6{slash}PWM-Pad20{slash}A6)") (class "Default")
      (node (ref "U$4") (pin "20/A6") (pinfunction "20/A6/PWM_20/A6") (pintype "bidirectional"))
    )
    (net (code "82") (name "unconnected-(U$4-21{slash}A7{slash}PWM-Pad21{slash}A7)") (class "Default")
      (node (ref "U$4") (pin "21/A7") (pinfunction "21/A7/PWM_21/A7") (pintype "bidirectional"))
    )
    (net (code "83") (name "unconnected-(U$4-22{slash}A8{slash}T{slash}PWM-Pad22{slash}A8)") (class "Default")
      (node (ref "U$4") (pin "22/A8") (pinfunction "22/A8/T/PWM_22/A8") (pintype "bidirectional"))
    )
    (net (code "84") (name "unconnected-(U$4-23{slash}A9{slash}T{slash}PWM-Pad23{slash}A9)") (class "Default")
      (node (ref "U$4") (pin "23/A9") (pinfunction "23/A9/T/PWM_23/A9") (pintype "bidirectional"))
    )
    (net (code "85") (name "unconnected-(U$4-Pad2)") (class "Default")
      (node (ref "U$4") (pin "2") (pinfunction "2_2") (pintype "bidirectional"))
    )
    (net (code "86") (name "unconnected-(U$5-0{slash}RX1{slash}T-Pad0)") (class "Default")
      (node (ref "U$5") (pin "0") (pinfunction "0/RX1/T_0") (pintype "bidirectional"))
    )
    (net (code "87") (name "unconnected-(U$5-1{slash}TX1{slash}T-Pad1)") (class "Default")
      (node (ref "U$5") (pin "1") (pinfunction "1/TX1/T_1") (pintype "bidirectional"))
    )
    (net (code "88") (name "unconnected-(U$5-3{slash}CAN-TX{slash}PWM-Pad3)") (class "Default")
      (node (ref "U$5") (pin "3") (pinfunction "3/CAN-TX/PWM_3") (pintype "bidirectional"))
    )
    (net (code "89") (name "unconnected-(U$5-4{slash}CAN-RX-PWM-Pad4)") (class "Default")
      (node (ref "U$5") (pin "4") (pinfunction "4/CAN-RX-PWM_4") (pintype "bidirectional"))
    )
    (net (code "90") (name "unconnected-(U$5-5{slash}PWM-Pad5)") (class "Default")
      (node (ref "U$5") (pin "5") (pinfunction "5/PWM_5") (pintype "bidirectional"))
    )
    (net (code "91") (name "unconnected-(U$5-6{slash}PWM-Pad6)") (class "Default")
      (node (ref "U$5") (pin "6") (pinfunction "6/PWM_6") (pintype "bidirectional"))
    )
    (net (code "92") (name "unconnected-(U$5-7{slash}RX3-Pad7)") (class "Default")
      (node (ref "U$5") (pin "7") (pinfunction "7/RX3_7") (pintype "bidirectional"))
    )
    (net (code "93") (name "unconnected-(U$5-8{slash}TX3-Pad8)") (class "Default")
      (node (ref "U$5") (pin "8") (pinfunction "8/TX3_8") (pintype "bidirectional"))
    )
    (net (code "94") (name "unconnected-(U$5-9{slash}RX2{slash}PWM-Pad9)") (class "Default")
      (node (ref "U$5") (pin "9") (pinfunction "9/RX2/PWM_9") (pintype "bidirectional"))
    )
    (net (code "95") (name "unconnected-(U$5-10{slash}TX2{slash}PWM-Pad10)") (class "Default")
      (node (ref "U$5") (pin "10") (pinfunction "10/TX2/PWM_10") (pintype "bidirectional"))
    )
    (net (code "96") (name "unconnected-(U$5-11{slash}MOSI-Pad11)") (class "Default")
      (node (ref "U$5") (pin "11") (pinfunction "11/MOSI_11") (pintype "bidirectional"))
    )
    (net (code "97") (name "unconnected-(U$5-12{slash}MISO-Pad12)") (class "Default")
      (node (ref "U$5") (pin "12") (pinfunction "12/MISO_12") (pintype "bidirectional"))
    )
    (net (code "98") (name "unconnected-(U$5-13{slash}SCK{slash}LED-Pad13)") (class "Default")
      (node (ref "U$5") (pin "13") (pinfunction "13/SCK/LED_13") (pintype "bidirectional"))
    )
    (net (code "99") (name "unconnected-(U$5-14{slash}A1-Pad14{slash}A0)") (class "Default")
      (node (ref "U$5") (pin "14/A0") (pinfunction "14/A1_14/A0") (pintype "bidirectional"))
    )
    (net (code "100") (name "unconnected-(U$5-15{slash}A1{slash}T-Pad15{slash}A1)") (class "Default")
      (node (ref "U$5") (pin "15/A1") (pinfunction "15/A1/T_15/A1") (pintype "bidirectional"))
    )
    (net (code "101") (name "unconnected-(U$5-16{slash}A2{slash}T-Pad16{slash}A2)") (class "Default")
      (node (ref "U$5") (pin "16/A2") (pinfunction "16/A2/T_16/A2") (pintype "bidirectional"))
    )
    (net (code "102") (name "unconnected-(U$5-17{slash}A3{slash}T-Pad17{slash}A3)") (class "Default")
      (node (ref "U$5") (pin "17/A3") (pinfunction "17/A3/T_17/A3") (pintype "bidirectional"))
    )
    (net (code "103") (name "unconnected-(U$5-20{slash}A6{slash}PWM-Pad20{slash}A6)") (class "Default")
      (node (ref "U$5") (pin "20/A6") (pinfunction "20/A6/PWM_20/A6") (pintype "bidirectional"))
    )
    (net (code "104") (name "unconnected-(U$5-21{slash}A7{slash}PWM-Pad21{slash}A7)") (class "Default")
      (node (ref "U$5") (pin "21/A7") (pinfunction "21/A7/PWM_21/A7") (pintype "bidirectional"))
    )
    (net (code "105") (name "unconnected-(U$5-22{slash}A8{slash}T{slash}PWM-Pad22{slash}A8)") (class "Default")
      (node (ref "U$5") (pin "22/A8") (pinfunction "22/A8/T/PWM_22/A8") (pintype "bidirectional"))
    )
    (net (code "106") (name "unconnected-(U$5-23{slash}A9{slash}T{slash}PWM-Pad23{slash}A9)") (class "Default")
      (node (ref "U$5") (pin "23/A9") (pinfunction "23/A9/T/PWM_23/A9") (pintype "bidirectional"))
    )
    (net (code "107") (name "unconnected-(U$5-Pad2)") (class "Default")
      (node (ref "U$5") (pin "2") (pinfunction "2_2") (pintype "bidirectional"))
    )
  )
)
